# SCH_SIM7670G.net
KiCad netlist of a schematic drawn in Altium Designer
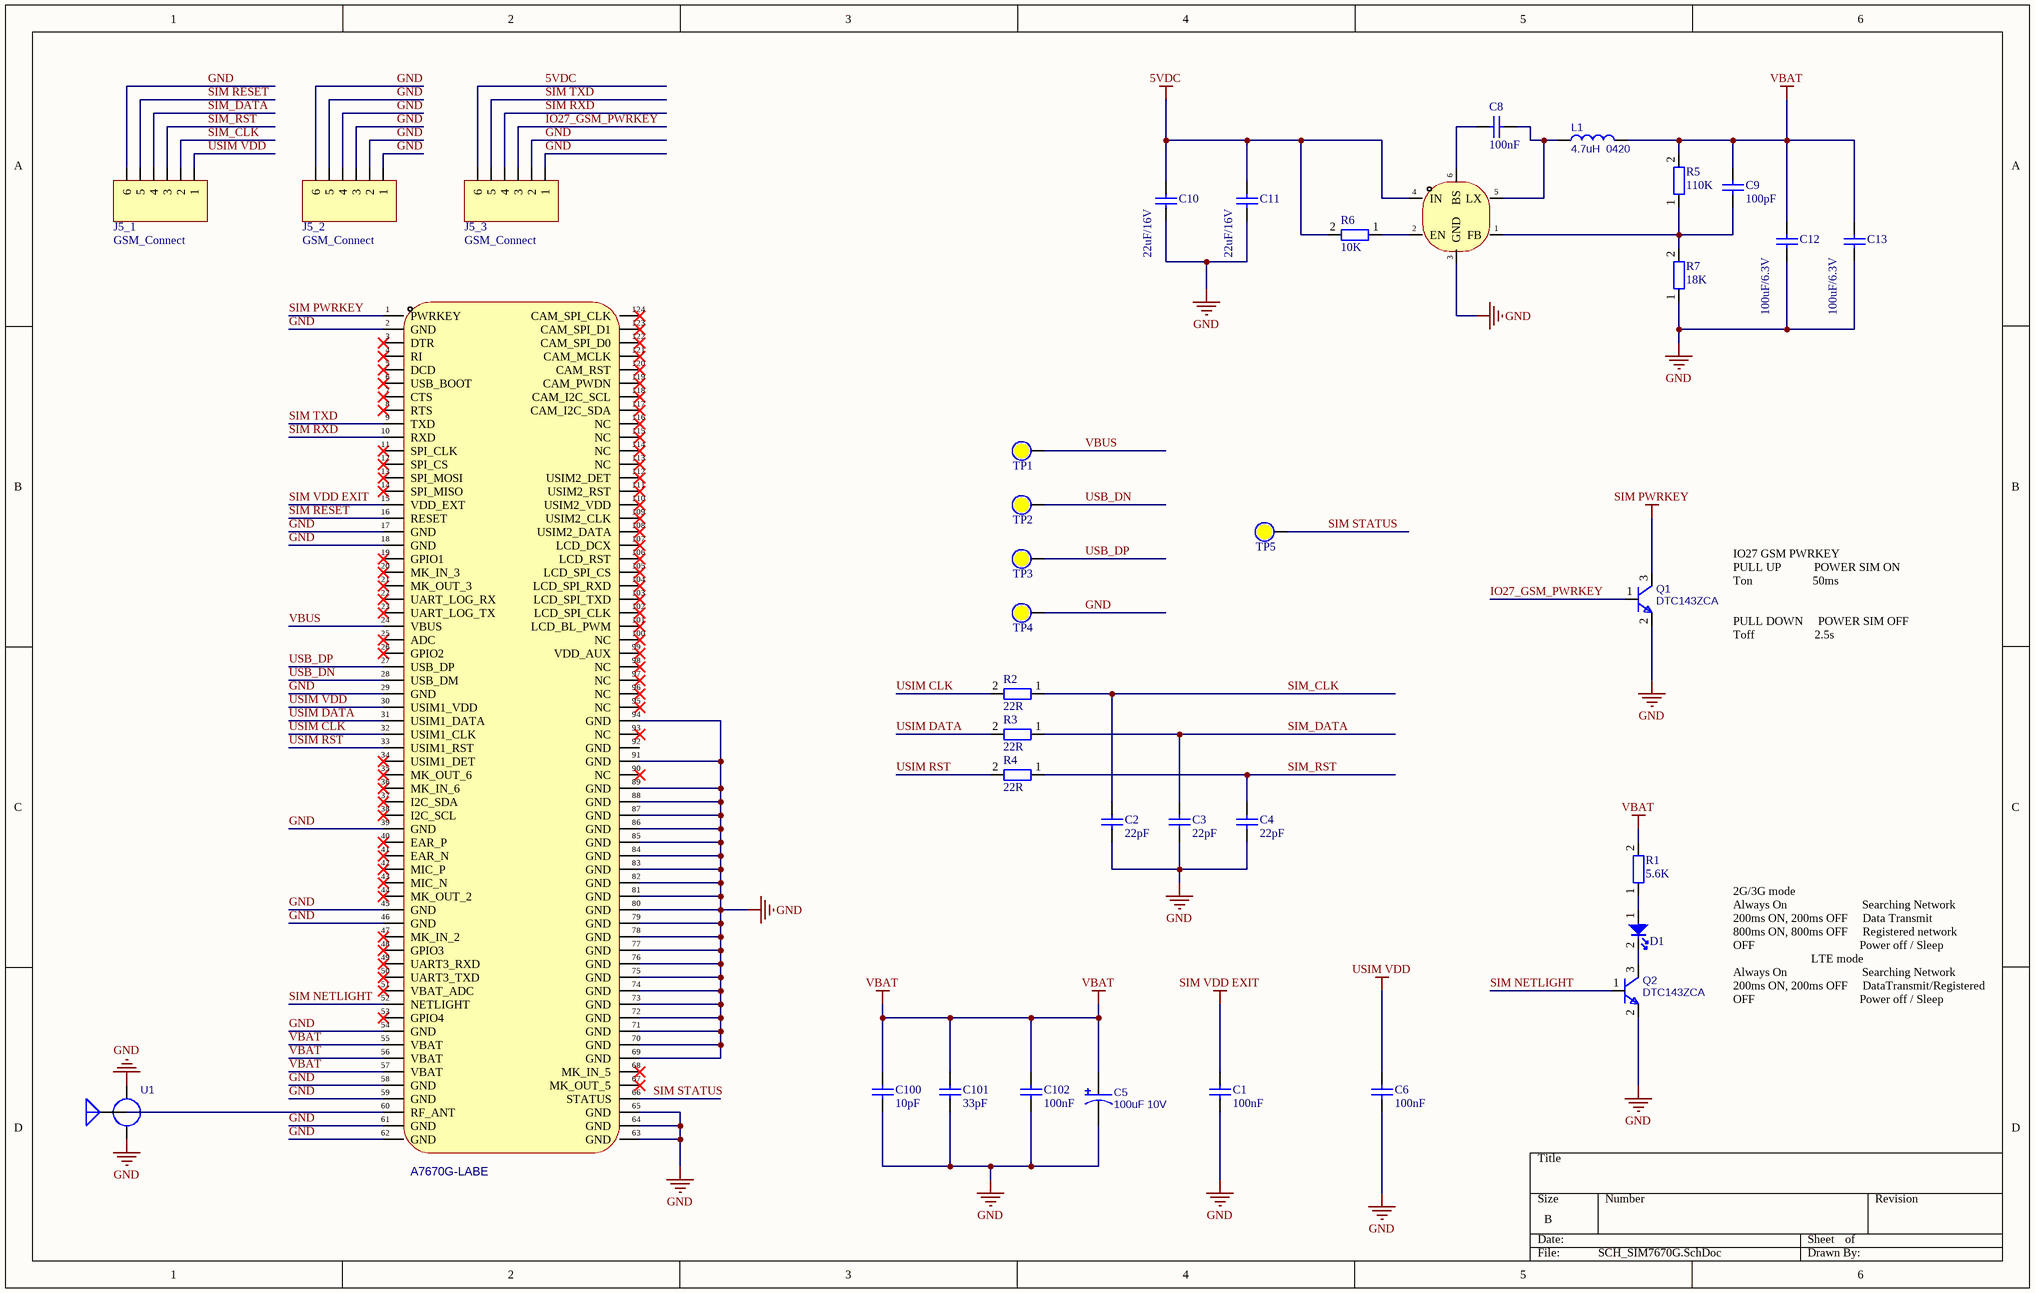
[diagram p0: SCH_SIM7670G.SchDoc]

(export (version "E")
  (design (tool "Eeschema 10.0.6"))
  (components
    (comp (ref "C1")
      (value "100nF")
      (footprint "CAP CERAMIC SMD 0402 TyPE 1005")
      (description "Capacitor")
      (libsource (lib "SCH_Library") (part "CAP104-100nF-50V"))
    )
    (comp (ref "C2")
      (value "22pF")
      (footprint "CAP CERAMIC SMD 0402 TyPE 1005")
      (description "Capacitor")
      (libsource (lib "SCH_Library") (part "CAP104-100nF-50V"))
    )
    (comp (ref "C3")
      (value "22pF")
      (footprint "CAP CERAMIC SMD 0402 TyPE 1005")
      (description "Capacitor")
      (libsource (lib "SCH_Library") (part "CAP104-100nF-50V"))
    )
    (comp (ref "C4")
      (value "22pF")
      (footprint "CAP CERAMIC SMD 0402 TyPE 1005")
      (description "Capacitor")
      (libsource (lib "SCH_Library") (part "CAP104-100nF-50V"))
    )
    (comp (ref "C5")
      (value "100uF 10V")
      (footprint "CAP TANTALUM SMD 3528-21 type B")
      (description "Aluminum Electrolytic Capacitors - Leaded ROHS")
      (fields
        (field (name "BOM_SUPPLIER PART") "C398835")
        (field (name "BOM_MANUFACTURER PART") "ERR1VM102G20OT")
        (field (name "CONTRIBUTOR") "LCSC")
      )
      (libsource (lib "SCH_AES_Library") (part "CAP ALU HOLD"))
    )
    (comp (ref "C6")
      (value "100nF")
      (footprint "CAP CERAMIC SMD 0402 TyPE 1005")
      (description "Capacitor")
      (libsource (lib "SCH_Library") (part "CAP104-100nF-50V"))
    )
    (comp (ref "C8")
      (value "100nF")
      (footprint "CAP CERAMIC SMD 0402 TyPE 1005")
      (description "Capacitor")
      (libsource (lib "SCH_Library") (part "CAP104-100nF-50V"))
    )
    (comp (ref "C9")
      (value "100pF")
      (footprint "CAP CERAMIC SMD 0402 TyPE 1005")
      (description "Capacitor")
      (libsource (lib "SCH_Library") (part "CAP104-100nF-50V"))
    )
    (comp (ref "C10")
      (value "22uF/16V")
      (footprint "CAP CERAMIC SMD 0603 TyPE 1608")
      (description "Capacitor")
      (libsource (lib "SCH_Library") (part "CAP104-100nF-50V"))
    )
    (comp (ref "C11")
      (value "22uF/16V")
      (footprint "CAP CERAMIC SMD 0603 TyPE 1608")
      (description "Capacitor")
      (libsource (lib "SCH_Library") (part "CAP104-100nF-50V"))
    )
    (comp (ref "C12")
      (value "100uF/6.3V")
      (footprint "CAP CERAMIC SMD 1206 TyPE 3216")
      (description "Capacitor")
      (libsource (lib "SCH_Library") (part "CAP104-100nF-50V"))
    )
    (comp (ref "C13")
      (value "100uF/6.3V")
      (footprint "CAP CERAMIC SMD 1206 TyPE 3216")
      (description "Capacitor")
      (libsource (lib "SCH_Library") (part "CAP104-100nF-50V"))
    )
    (comp (ref "C100")
      (value "10pF")
      (footprint "CAP CERAMIC SMD 0402 TyPE 1005")
      (description "Capacitor")
      (libsource (lib "SCH_Library") (part "CAP104-100nF-50V"))
    )
    (comp (ref "C101")
      (value "33pF")
      (footprint "CAP CERAMIC SMD 0402 TyPE 1005")
      (description "Capacitor")
      (libsource (lib "SCH_Library") (part "CAP104-100nF-50V"))
    )
    (comp (ref "C102")
      (value "100nF")
      (footprint "CAP CERAMIC SMD 0402 TyPE 1005")
      (description "Capacitor")
      (libsource (lib "SCH_Library") (part "CAP104-100nF-50V"))
    )
    (comp (ref "D1")
      (value "LED")
      (footprint "LED SMD GREEN TYPE 0603")
      (description "Emerald 0805 Light Emitting Diodes (LED) ROHS")
      (libsource (lib "SCH_AES_Library") (part "LED SMD 0805"))
    )
    (comp (ref "J5_1")
      (value "GSM_Connect")
      (footprint "CONNECTORS FEMALE HEADERS 1X6 2.0 TYPE STRAIGHT SMD")
      (description "Cắm")
      (libsource (lib "Altium_Lib") (part "JP 1x6 2.54 Duc Thang"))
    )
    (comp (ref "J5_2")
      (value "GSM_Connect")
      (footprint "CONNECTORS FEMALE HEADERS 1X6 2.0 TYPE STRAIGHT SMD")
      (description "Cắm")
      (libsource (lib "Altium_Lib") (part "JP 1x6 2.54 Duc Thang"))
    )
    (comp (ref "J5_3")
      (value "GSM_Connect")
      (footprint "CONNECTORS FEMALE HEADERS 1X6 2.0 TYPE STRAIGHT SMD")
      (description "Cắm")
      (libsource (lib "Altium_Lib") (part "JP 1x6 2.54 Duc Thang"))
    )
    (comp (ref "L1")
      (value "4.7uH  0420")
      (footprint "INDUCTORS SMD 0420")
      (fields
        (field (name "BOM_SUPPLIER PART") "C578001")
        (field (name "BOM_MANUFACTURER PART") "SCHF160808H47NJT")
        (field (name "CONTRIBUTOR") "LCSC")
      )
      (libsource (lib "SCH_AES_Library") (part "INDUCTORS SMD"))
    )
    (comp (ref "Q1")
      (value "DTC143ZCA")
      (footprint "SOT-23")
      (description "SOT-23 Bipolar Transistors npn - BJT ROHS")
      (fields
        (field (name "BOM_SUPPLIER PART") "C5156716")
        (field (name "BOM_MANUFACTURER PART") "MMBT3904")
        (field (name "CONTRIBUTOR") "lcsc")
      )
      (libsource (lib "SCH_AES_Library") (part "TRANSISTOR SMD NPN"))
    )
    (comp (ref "Q2")
      (value "DTC143ZCA")
      (footprint "SOT-23")
      (description "SOT-23 Bipolar Transistors npn - BJT ROHS")
      (fields
        (field (name "BOM_SUPPLIER PART") "C5156716")
        (field (name "BOM_MANUFACTURER PART") "MMBT3904")
        (field (name "CONTRIBUTOR") "lcsc")
      )
      (libsource (lib "SCH_AES_Library") (part "TRANSISTOR SMD NPN"))
    )
    (comp (ref "R1")
      (value "5.6K")
      (footprint "RES CHIPS SMD 0402 TYPE 1005")
      (description "±1% - Chip Resistor - Surface Mount ROHS")
      (libsource (lib "SCH_Library") (part "RES 0603 1%_"))
    )
    (comp (ref "R2")
      (value "22R")
      (footprint "RES CHIPS SMD 0402 TYPE 1005")
      (description "±1% - Chip Resistor - Surface Mount ROHS")
      (libsource (lib "SCH_Library") (part "RES 0603 1%_"))
    )
    (comp (ref "R3")
      (value "22R")
      (footprint "RES CHIPS SMD 0402 TYPE 1005")
      (description "±1% - Chip Resistor - Surface Mount ROHS")
      (libsource (lib "SCH_Library") (part "RES 0603 1%_"))
    )
    (comp (ref "R4")
      (value "22R")
      (footprint "RES CHIPS SMD 0402 TYPE 1005")
      (description "±1% - Chip Resistor - Surface Mount ROHS")
      (libsource (lib "SCH_Library") (part "RES 0603 1%_"))
    )
    (comp (ref "R5")
      (value "110K")
      (footprint "RES CHIPS SMD 0402 TYPE 1005")
      (description "±1% - Chip Resistor - Surface Mount ROHS")
      (libsource (lib "SCH_Library") (part "RES 0603 1%_"))
    )
    (comp (ref "R6")
      (value "10K")
      (footprint "RES CHIPS SMD 0402 TYPE 1005")
      (description "±1% - Chip Resistor - Surface Mount ROHS")
      (libsource (lib "SCH_Library") (part "RES 0603 1%_"))
    )
    (comp (ref "R7")
      (value "18K")
      (footprint "RES CHIPS SMD 0402 TYPE 1005")
      (description "±1% - Chip Resistor - Surface Mount ROHS")
      (libsource (lib "SCH_Library") (part "RES 0603 1%_"))
    )
    (comp (ref "TP1")
      (value "~")
      (footprint "TEST POINT 4")
      (description "Test Point")
      (libsource (lib "SCH_AES_Library") (part "TEST POINT"))
    )
    (comp (ref "TP2")
      (value "~")
      (footprint "TEST POINT 4")
      (description "Test Point")
      (libsource (lib "SCH_AES_Library") (part "TEST POINT"))
    )
    (comp (ref "TP3")
      (value "~")
      (footprint "TEST POINT 4")
      (description "Test Point")
      (libsource (lib "SCH_AES_Library") (part "TEST POINT"))
    )
    (comp (ref "TP4")
      (value "~")
      (footprint "TEST POINT 4")
      (description "Test Point")
      (libsource (lib "SCH_AES_Library") (part "TEST POINT"))
    )
    (comp (ref "TP5")
      (value "~")
      (footprint "TEST POINT 4")
      (description "Test Point")
      (libsource (lib "SCH_AES_Library") (part "TEST POINT"))
    )
    (comp (ref "U1")
      (value "~")
      (footprint "CONNECTORS RF SMD TYPE IPEX")
      (description "SMD RF Connectors / Coaxial Connectors ROHS")
      (fields
        (field (name "BOM_SUPPLIER PART") "C3151745")
        (field (name "BOM_MANUFACTURER PART") "IPEX1-TXZ 142")
        (field (name "CONTRIBUTOR") "lcsc")
      )
      (libsource (lib "SCH_AES_Library") (part "CONNECTORS RF SMD"))
    )
    (comp (ref "U2")
      (value "A7670G-LABE")
      (footprint "Modules SIM7670G")
      (fields (field (name "MANUFACTURER") "SIMCOM(芯讯通无线科技)"))
      (libsource (lib "SCH_AES_Library") (part "MODULES SIM A7670G-LABE"))
    )
    (comp (ref "U3")
      (value "SY8105IADC")
      (footprint "SOT-23-6")
      (fields (field (name "MANUFACTURER") "silergy(矽力杰)"))
      (libsource (lib "SCH_AES_Library") (part "SY8105IADC"))
    )
  )
  (nets
    (net (code "1") (name "/IO27_GSM_PWRKEY") (class "Default")
      (node (ref "J5_3") (pin "3") (pinfunction "3_3") (pintype "passive"))
      (node (ref "Q1") (pin "1") (pinfunction "B_1") (pintype "passive"))
    )
    (net (code "2") (name "/SIM NETLIGHT") (class "Default")
      (node (ref "Q2") (pin "1") (pinfunction "B_1") (pintype "passive"))
      (node (ref "U2") (pin "52") (pinfunction "NETLIGHT_52") (pintype "passive"))
    )
    (net (code "3") (name "/SIM RESET") (class "Default")
      (node (ref "J5_1") (pin "5") (pinfunction "5_5") (pintype "passive"))
      (node (ref "U2") (pin "16") (pinfunction "RESET_16") (pintype "passive"))
    )
    (net (code "4") (name "/SIM RXD") (class "Default")
      (node (ref "J5_3") (pin "4") (pinfunction "4_4") (pintype "passive"))
      (node (ref "U2") (pin "10") (pinfunction "RXD_10") (pintype "passive"))
    )
    (net (code "5") (name "/SIM STATUS") (class "Default")
      (node (ref "TP5") (pin "0") (pinfunction "0_0") (pintype "passive"))
      (node (ref "U2") (pin "66") (pinfunction "STATUS_66") (pintype "passive"))
    )
    (net (code "6") (name "/SIM TXD") (class "Default")
      (node (ref "J5_3") (pin "5") (pinfunction "5_5") (pintype "passive"))
      (node (ref "U2") (pin "9") (pinfunction "TXD_9") (pintype "passive"))
    )
    (net (code "7") (name "/SIM_CLK") (class "Default")
      (node (ref "C2") (pin "1") (pinfunction "1_1") (pintype "passive"))
      (node (ref "J5_1") (pin "2") (pinfunction "2_2") (pintype "passive"))
      (node (ref "R2") (pin "1") (pinfunction "1_1") (pintype "passive"))
    )
    (net (code "8") (name "/SIM_DATA") (class "Default")
      (node (ref "C3") (pin "2") (pinfunction "2_2") (pintype "passive"))
      (node (ref "J5_1") (pin "4") (pinfunction "4_4") (pintype "passive"))
      (node (ref "R3") (pin "1") (pinfunction "1_1") (pintype "passive"))
    )
    (net (code "9") (name "/SIM_RST") (class "Default")
      (node (ref "C4") (pin "2") (pinfunction "2_2") (pintype "passive"))
      (node (ref "J5_1") (pin "3") (pinfunction "3_3") (pintype "passive"))
      (node (ref "R4") (pin "1") (pinfunction "1_1") (pintype "passive"))
    )
    (net (code "10") (name "/USB_DN") (class "Default")
      (node (ref "TP2") (pin "0") (pinfunction "0_0") (pintype "passive"))
      (node (ref "U2") (pin "28") (pinfunction "USB_DM_28") (pintype "passive"))
    )
    (net (code "11") (name "/USB_DP") (class "Default")
      (node (ref "TP3") (pin "0") (pinfunction "0_0") (pintype "passive"))
      (node (ref "U2") (pin "27") (pinfunction "USB_DP_27") (pintype "passive"))
    )
    (net (code "12") (name "/USIM CLK") (class "Default")
      (node (ref "R2") (pin "2") (pinfunction "2_2") (pintype "passive"))
      (node (ref "U2") (pin "32") (pinfunction "USIM1_CLK_32") (pintype "passive"))
    )
    (net (code "13") (name "/USIM DATA") (class "Default")
      (node (ref "R3") (pin "2") (pinfunction "2_2") (pintype "passive"))
      (node (ref "U2") (pin "31") (pinfunction "USIM1_DATA_31") (pintype "passive"))
    )
    (net (code "14") (name "/USIM RST") (class "Default")
      (node (ref "R4") (pin "2") (pinfunction "2_2") (pintype "passive"))
      (node (ref "U2") (pin "33") (pinfunction "USIM1_RST_33") (pintype "passive"))
    )
    (net (code "15") (name "/VBUS") (class "Default")
      (node (ref "TP1") (pin "0") (pinfunction "0_0") (pintype "passive"))
      (node (ref "U2") (pin "24") (pinfunction "VBUS_24") (pintype "passive"))
    )
    (net (code "16") (name "5VDC") (class "Default")
      (node (ref "C10") (pin "2") (pinfunction "2_2") (pintype "passive"))
      (node (ref "C11") (pin "2") (pinfunction "2_2") (pintype "passive"))
      (node (ref "J5_3") (pin "6") (pinfunction "6_6") (pintype "passive"))
      (node (ref "R6") (pin "2") (pinfunction "2_2") (pintype "passive"))
      (node (ref "U3") (pin "4") (pinfunction "IN_4") (pintype "passive"))
    )
    (net (code "17") (name "GND") (class "Default")
      (node (ref "C1") (pin "1") (pinfunction "1_1") (pintype "passive"))
      (node (ref "C10") (pin "1") (pinfunction "1_1") (pintype "passive"))
      (node (ref "C100") (pin "1") (pinfunction "1_1") (pintype "passive"))
      (node (ref "C101") (pin "1") (pinfunction "1_1") (pintype "passive"))
      (node (ref "C102") (pin "1") (pinfunction "1_1") (pintype "passive"))
      (node (ref "C11") (pin "1") (pinfunction "1_1") (pintype "passive"))
      (node (ref "C12") (pin "1") (pinfunction "1_1") (pintype "passive"))
      (node (ref "C13") (pin "1") (pinfunction "1_1") (pintype "passive"))
      (node (ref "C2") (pin "2") (pinfunction "2_2") (pintype "passive"))
      (node (ref "C3") (pin "1") (pinfunction "1_1") (pintype "passive"))
      (node (ref "C4") (pin "1") (pinfunction "1_1") (pintype "passive"))
      (node (ref "C5") (pin "2") (pinfunction "2_2") (pintype "passive"))
      (node (ref "C6") (pin "1") (pinfunction "1_1") (pintype "passive"))
      (node (ref "J5_1") (pin "6") (pinfunction "6_6") (pintype "passive"))
      (node (ref "J5_2") (pin "1") (pinfunction "1_1") (pintype "passive"))
      (node (ref "J5_2") (pin "2") (pinfunction "2_2") (pintype "passive"))
      (node (ref "J5_2") (pin "3") (pinfunction "3_3") (pintype "passive"))
      (node (ref "J5_2") (pin "4") (pinfunction "4_4") (pintype "passive"))
      (node (ref "J5_2") (pin "5") (pinfunction "5_5") (pintype "passive"))
      (node (ref "J5_2") (pin "6") (pinfunction "6_6") (pintype "passive"))
      (node (ref "J5_3") (pin "1") (pinfunction "1_1") (pintype "passive"))
      (node (ref "J5_3") (pin "2") (pinfunction "2_2") (pintype "passive"))
      (node (ref "Q1") (pin "2") (pinfunction "E_2") (pintype "passive"))
      (node (ref "Q2") (pin "2") (pinfunction "E_2") (pintype "passive"))
      (node (ref "R7") (pin "1") (pinfunction "1_1") (pintype "passive"))
      (node (ref "TP4") (pin "0") (pinfunction "0_0") (pintype "passive"))
      (node (ref "U1") (pin "2") (pinfunction "2_2") (pintype "passive"))
      (node (ref "U1") (pin "3") (pinfunction "3_3") (pintype "passive"))
      (node (ref "U2") (pin "17") (pinfunction "GND_17") (pintype "passive"))
      (node (ref "U2") (pin "18") (pinfunction "GND_18") (pintype "passive"))
      (node (ref "U2") (pin "2") (pinfunction "GND_2") (pintype "passive"))
      (node (ref "U2") (pin "29") (pinfunction "GND_29") (pintype "passive"))
      (node (ref "U2") (pin "39") (pinfunction "GND_39") (pintype "passive"))
      (node (ref "U2") (pin "45") (pinfunction "GND_45") (pintype "passive"))
      (node (ref "U2") (pin "46") (pinfunction "GND_46") (pintype "passive"))
      (node (ref "U2") (pin "54") (pinfunction "GND_54") (pintype "passive"))
      (node (ref "U2") (pin "58") (pinfunction "GND_58") (pintype "passive"))
      (node (ref "U2") (pin "59") (pinfunction "GND_59") (pintype "passive"))
      (node (ref "U2") (pin "61") (pinfunction "GND_61") (pintype "passive"))
      (node (ref "U2") (pin "62") (pinfunction "GND_62") (pintype "passive"))
      (node (ref "U2") (pin "63") (pinfunction "GND_63") (pintype "passive"))
      (node (ref "U2") (pin "64") (pinfunction "GND_64") (pintype "passive"))
      (node (ref "U2") (pin "65") (pinfunction "GND_65") (pintype "passive"))
      (node (ref "U2") (pin "69") (pinfunction "GND_69") (pintype "passive"))
      (node (ref "U2") (pin "70") (pinfunction "GND_70") (pintype "passive"))
      (node (ref "U2") (pin "71") (pinfunction "GND_71") (pintype "passive"))
      (node (ref "U2") (pin "72") (pinfunction "GND_72") (pintype "passive"))
      (node (ref "U2") (pin "73") (pinfunction "GND_73") (pintype "passive"))
      (node (ref "U2") (pin "74") (pinfunction "GND_74") (pintype "passive"))
      (node (ref "U2") (pin "75") (pinfunction "GND_75") (pintype "passive"))
      (node (ref "U2") (pin "76") (pinfunction "GND_76") (pintype "passive"))
      (node (ref "U2") (pin "77") (pinfunction "GND_77") (pintype "passive"))
      (node (ref "U2") (pin "78") (pinfunction "GND_78") (pintype "passive"))
      (node (ref "U2") (pin "79") (pinfunction "GND_79") (pintype "passive"))
      (node (ref "U2") (pin "80") (pinfunction "GND_80") (pintype "passive"))
      (node (ref "U2") (pin "81") (pinfunction "GND_81") (pintype "passive"))
      (node (ref "U2") (pin "82") (pinfunction "GND_82") (pintype "passive"))
      (node (ref "U2") (pin "83") (pinfunction "GND_83") (pintype "passive"))
      (node (ref "U2") (pin "84") (pinfunction "GND_84") (pintype "passive"))
      (node (ref "U2") (pin "85") (pinfunction "GND_85") (pintype "passive"))
      (node (ref "U2") (pin "86") (pinfunction "GND_86") (pintype "passive"))
      (node (ref "U2") (pin "87") (pinfunction "GND_87") (pintype "passive"))
      (node (ref "U2") (pin "88") (pinfunction "GND_88") (pintype "passive"))
      (node (ref "U2") (pin "89") (pinfunction "GND_89") (pintype "passive"))
      (node (ref "U2") (pin "91") (pinfunction "GND_91") (pintype "passive"))
      (node (ref "U2") (pin "94") (pinfunction "GND_94") (pintype "passive"))
      (node (ref "U3") (pin "3") (pinfunction "GND_3") (pintype "passive"))
    )
    (net (code "18") (name "Net-(D1-Pad1)") (class "Default")
      (node (ref "D1") (pin "1") (pinfunction "1_1") (pintype "passive"))
      (node (ref "R1") (pin "1") (pinfunction "1_1") (pintype "passive"))
    )
    (net (code "19") (name "Net-(Q2-C)") (class "Default")
      (node (ref "D1") (pin "2") (pinfunction "2_2") (pintype "passive"))
      (node (ref "Q2") (pin "3") (pinfunction "C_3") (pintype "passive"))
    )
    (net (code "20") (name "Net-(U2-RF_ANT)") (class "Default")
      (node (ref "U1") (pin "1") (pinfunction "1_1") (pintype "passive"))
      (node (ref "U2") (pin "60") (pinfunction "RF_ANT_60") (pintype "passive"))
    )
    (net (code "21") (name "Net-(U3-BS)") (class "Default")
      (node (ref "C8") (pin "2") (pinfunction "2_2") (pintype "passive"))
      (node (ref "U3") (pin "6") (pinfunction "BS_6") (pintype "passive"))
    )
    (net (code "22") (name "Net-(U3-EN)") (class "Default")
      (node (ref "R6") (pin "1") (pinfunction "1_1") (pintype "passive"))
      (node (ref "U3") (pin "2") (pinfunction "EN_2") (pintype "passive"))
    )
    (net (code "23") (name "Net-(U3-FB)") (class "Default")
      (node (ref "C9") (pin "1") (pinfunction "1_1") (pintype "passive"))
      (node (ref "R5") (pin "1") (pinfunction "1_1") (pintype "passive"))
      (node (ref "R7") (pin "2") (pinfunction "2_2") (pintype "passive"))
      (node (ref "U3") (pin "1") (pinfunction "FB_1") (pintype "passive"))
    )
    (net (code "24") (name "Net-(U3-LX)") (class "Default")
      (node (ref "C8") (pin "1") (pinfunction "1_1") (pintype "passive"))
      (node (ref "L1") (pin "1") (pinfunction "1_1") (pintype "passive"))
      (node (ref "U3") (pin "5") (pinfunction "LX_5") (pintype "passive"))
    )
    (net (code "25") (name "SIM PWRKEY") (class "Default")
      (node (ref "Q1") (pin "3") (pinfunction "C_3") (pintype "passive"))
      (node (ref "U2") (pin "1") (pinfunction "PWRKEY_1") (pintype "passive"))
    )
    (net (code "26") (name "SIM VDD EXIT") (class "Default")
      (node (ref "C1") (pin "2") (pinfunction "2_2") (pintype "passive"))
      (node (ref "U2") (pin "15") (pinfunction "VDD_EXT_15") (pintype "passive"))
    )
    (net (code "27") (name "USIM VDD") (class "Default")
      (node (ref "C6") (pin "2") (pinfunction "2_2") (pintype "passive"))
      (node (ref "J5_1") (pin "1") (pinfunction "1_1") (pintype "passive"))
      (node (ref "U2") (pin "30") (pinfunction "USIM1_VDD_30") (pintype "passive"))
    )
    (net (code "28") (name "VBAT") (class "Default")
      (node (ref "C100") (pin "2") (pinfunction "2_2") (pintype "passive"))
      (node (ref "C101") (pin "2") (pinfunction "2_2") (pintype "passive"))
      (node (ref "C102") (pin "2") (pinfunction "2_2") (pintype "passive"))
      (node (ref "C12") (pin "2") (pinfunction "2_2") (pintype "passive"))
      (node (ref "C13") (pin "2") (pinfunction "2_2") (pintype "passive"))
      (node (ref "C5") (pin "1") (pinfunction "1_1") (pintype "passive"))
      (node (ref "C9") (pin "2") (pinfunction "2_2") (pintype "passive"))
      (node (ref "L1") (pin "2") (pinfunction "2_2") (pintype "passive"))
      (node (ref "R1") (pin "2") (pinfunction "2_2") (pintype "passive"))
      (node (ref "R5") (pin "2") (pinfunction "2_2") (pintype "passive"))
      (node (ref "U2") (pin "55") (pinfunction "VBAT_55") (pintype "passive"))
      (node (ref "U2") (pin "56") (pinfunction "VBAT_56") (pintype "passive"))
      (node (ref "U2") (pin "57") (pinfunction "VBAT_57") (pintype "passive"))
    )
    (net (code "29") (name "unconnected-(U2-ADC-Pad25)") (class "Default")
      (node (ref "U2") (pin "25") (pinfunction "ADC_25") (pintype "passive+no_connect"))
    )
    (net (code "30") (name "unconnected-(U2-CAM_I2C_SCL-Pad118)") (class "Default")
      (node (ref "U2") (pin "118") (pinfunction "CAM_I2C_SCL_118") (pintype "passive+no_connect"))
    )
    (net (code "31") (name "unconnected-(U2-CAM_I2C_SDA-Pad117)") (class "Default")
      (node (ref "U2") (pin "117") (pinfunction "CAM_I2C_SDA_117") (pintype "passive+no_connect"))
    )
    (net (code "32") (name "unconnected-(U2-CAM_MCLK-Pad121)") (class "Default")
      (node (ref "U2") (pin "121") (pinfunction "CAM_MCLK_121") (pintype "passive+no_connect"))
    )
    (net (code "33") (name "unconnected-(U2-CAM_PWDN-Pad119)") (class "Default")
      (node (ref "U2") (pin "119") (pinfunction "CAM_PWDN_119") (pintype "passive+no_connect"))
    )
    (net (code "34") (name "unconnected-(U2-CAM_RST-Pad120)") (class "Default")
      (node (ref "U2") (pin "120") (pinfunction "CAM_RST_120") (pintype "passive+no_connect"))
    )
    (net (code "35") (name "unconnected-(U2-CAM_SPI_CLK-Pad124)") (class "Default")
      (node (ref "U2") (pin "124") (pinfunction "CAM_SPI_CLK_124") (pintype "passive+no_connect"))
    )
    (net (code "36") (name "unconnected-(U2-CAM_SPI_D0-Pad122)") (class "Default")
      (node (ref "U2") (pin "122") (pinfunction "CAM_SPI_D0_122") (pintype "passive+no_connect"))
    )
    (net (code "37") (name "unconnected-(U2-CAM_SPI_D1-Pad123)") (class "Default")
      (node (ref "U2") (pin "123") (pinfunction "CAM_SPI_D1_123") (pintype "passive+no_connect"))
    )
    (net (code "38") (name "unconnected-(U2-CTS-Pad7)") (class "Default")
      (node (ref "U2") (pin "7") (pinfunction "CTS_7") (pintype "passive+no_connect"))
    )
    (net (code "39") (name "unconnected-(U2-DCD-Pad5)") (class "Default")
      (node (ref "U2") (pin "5") (pinfunction "DCD_5") (pintype "passive+no_connect"))
    )
    (net (code "40") (name "unconnected-(U2-DTR-Pad3)") (class "Default")
      (node (ref "U2") (pin "3") (pinfunction "DTR_3") (pintype "passive+no_connect"))
    )
    (net (code "41") (name "unconnected-(U2-EAR_N-Pad41)") (class "Default")
      (node (ref "U2") (pin "41") (pinfunction "EAR_N_41") (pintype "passive+no_connect"))
    )
    (net (code "42") (name "unconnected-(U2-EAR_P-Pad40)") (class "Default")
      (node (ref "U2") (pin "40") (pinfunction "EAR_P_40") (pintype "passive+no_connect"))
    )
    (net (code "43") (name "unconnected-(U2-GND-Pad92)") (class "Default")
      (node (ref "U2") (pin "92") (pinfunction "GND_92") (pintype "passive"))
    )
    (net (code "44") (name "unconnected-(U2-GPIO1-Pad19)") (class "Default")
      (node (ref "U2") (pin "19") (pinfunction "GPIO1_19") (pintype "passive+no_connect"))
    )
    (net (code "45") (name "unconnected-(U2-GPIO2-Pad26)") (class "Default")
      (node (ref "U2") (pin "26") (pinfunction "GPIO2_26") (pintype "passive+no_connect"))
    )
    (net (code "46") (name "unconnected-(U2-GPIO3-Pad48)") (class "Default")
      (node (ref "U2") (pin "48") (pinfunction "GPIO3_48") (pintype "passive+no_connect"))
    )
    (net (code "47") (name "unconnected-(U2-GPIO4-Pad53)") (class "Default")
      (node (ref "U2") (pin "53") (pinfunction "GPIO4_53") (pintype "passive+no_connect"))
    )
    (net (code "48") (name "unconnected-(U2-I2C_SCL-Pad38)") (class "Default")
      (node (ref "U2") (pin "38") (pinfunction "I2C_SCL_38") (pintype "passive+no_connect"))
    )
    (net (code "49") (name "unconnected-(U2-I2C_SDA-Pad37)") (class "Default")
      (node (ref "U2") (pin "37") (pinfunction "I2C_SDA_37") (pintype "passive+no_connect"))
    )
    (net (code "50") (name "unconnected-(U2-LCD_BL_PWM-Pad101)") (class "Default")
      (node (ref "U2") (pin "101") (pinfunction "LCD_BL_PWM_101") (pintype "passive+no_connect"))
    )
    (net (code "51") (name "unconnected-(U2-LCD_DCX-Pad107)") (class "Default")
      (node (ref "U2") (pin "107") (pinfunction "LCD_DCX_107") (pintype "passive+no_connect"))
    )
    (net (code "52") (name "unconnected-(U2-LCD_RST-Pad106)") (class "Default")
      (node (ref "U2") (pin "106") (pinfunction "LCD_RST_106") (pintype "passive+no_connect"))
    )
    (net (code "53") (name "unconnected-(U2-LCD_SPI_CLK-Pad102)") (class "Default")
      (node (ref "U2") (pin "102") (pinfunction "LCD_SPI_CLK_102") (pintype "passive+no_connect"))
    )
    (net (code "54") (name "unconnected-(U2-LCD_SPI_CS-Pad105)") (class "Default")
      (node (ref "U2") (pin "105") (pinfunction "LCD_SPI_CS_105") (pintype "passive+no_connect"))
    )
    (net (code "55") (name "unconnected-(U2-LCD_SPI_RXD-Pad104)") (class "Default")
      (node (ref "U2") (pin "104") (pinfunction "LCD_SPI_RXD_104") (pintype "passive+no_connect"))
    )
    (net (code "56") (name "unconnected-(U2-LCD_SPI_TXD-Pad103)") (class "Default")
      (node (ref "U2") (pin "103") (pinfunction "LCD_SPI_TXD_103") (pintype "passive+no_connect"))
    )
    (net (code "57") (name "unconnected-(U2-MIC_N-Pad43)") (class "Default")
      (node (ref "U2") (pin "43") (pinfunction "MIC_N_43") (pintype "passive+no_connect"))
    )
    (net (code "58") (name "unconnected-(U2-MIC_P-Pad42)") (class "Default")
      (node (ref "U2") (pin "42") (pinfunction "MIC_P_42") (pintype "passive+no_connect"))
    )
    (net (code "59") (name "unconnected-(U2-MK_IN_2-Pad47)") (class "Default")
      (node (ref "U2") (pin "47") (pinfunction "MK_IN_2_47") (pintype "passive+no_connect"))
    )
    (net (code "60") (name "unconnected-(U2-MK_IN_3-Pad20)") (class "Default")
      (node (ref "U2") (pin "20") (pinfunction "MK_IN_3_20") (pintype "passive+no_connect"))
    )
    (net (code "61") (name "unconnected-(U2-MK_IN_5-Pad68)") (class "Default")
      (node (ref "U2") (pin "68") (pinfunction "MK_IN_5_68") (pintype "passive+no_connect"))
    )
    (net (code "62") (name "unconnected-(U2-MK_IN_6-Pad36)") (class "Default")
      (node (ref "U2") (pin "36") (pinfunction "MK_IN_6_36") (pintype "passive+no_connect"))
    )
    (net (code "63") (name "unconnected-(U2-MK_OUT_2-Pad44)") (class "Default")
      (node (ref "U2") (pin "44") (pinfunction "MK_OUT_2_44") (pintype "passive+no_connect"))
    )
    (net (code "64") (name "unconnected-(U2-MK_OUT_3-Pad21)") (class "Default")
      (node (ref "U2") (pin "21") (pinfunction "MK_OUT_3_21") (pintype "passive+no_connect"))
    )
    (net (code "65") (name "unconnected-(U2-MK_OUT_5-Pad67)") (class "Default")
      (node (ref "U2") (pin "67") (pinfunction "MK_OUT_5_67") (pintype "passive+no_connect"))
    )
    (net (code "66") (name "unconnected-(U2-MK_OUT_6-Pad35)") (class "Default")
      (node (ref "U2") (pin "35") (pinfunction "MK_OUT_6_35") (pintype "passive+no_connect"))
    )
    (net (code "67") (name "unconnected-(U2-NC-Pad90)") (class "Default")
      (node (ref "U2") (pin "90") (pinfunction "NC_90") (pintype "passive+no_connect"))
    )
    (net (code "68") (name "unconnected-(U2-NC-Pad93)") (class "Default")
      (node (ref "U2") (pin "93") (pinfunction "NC_93") (pintype "passive+no_connect"))
    )
    (net (code "69") (name "unconnected-(U2-NC-Pad95)") (class "Default")
      (node (ref "U2") (pin "95") (pinfunction "NC_95") (pintype "passive+no_connect"))
    )
    (net (code "70") (name "unconnected-(U2-NC-Pad96)") (class "Default")
      (node (ref "U2") (pin "96") (pinfunction "NC_96") (pintype "passive+no_connect"))
    )
    (net (code "71") (name "unconnected-(U2-NC-Pad97)") (class "Default")
      (node (ref "U2") (pin "97") (pinfunction "NC_97") (pintype "passive+no_connect"))
    )
    (net (code "72") (name "unconnected-(U2-NC-Pad98)") (class "Default")
      (node (ref "U2") (pin "98") (pinfunction "NC_98") (pintype "passive+no_connect"))
    )
    (net (code "73") (name "unconnected-(U2-NC-Pad100)") (class "Default")
      (node (ref "U2") (pin "100") (pinfunction "NC_100") (pintype "passive+no_connect"))
    )
    (net (code "74") (name "unconnected-(U2-NC-Pad113)") (class "Default")
      (node (ref "U2") (pin "113") (pinfunction "NC_113") (pintype "passive+no_connect"))
    )
    (net (code "75") (name "unconnected-(U2-NC-Pad114)") (class "Default")
      (node (ref "U2") (pin "114") (pinfunction "NC_114") (pintype "passive+no_connect"))
    )
    (net (code "76") (name "unconnected-(U2-NC-Pad115)") (class "Default")
      (node (ref "U2") (pin "115") (pinfunction "NC_115") (pintype "passive+no_connect"))
    )
    (net (code "77") (name "unconnected-(U2-NC-Pad116)") (class "Default")
      (node (ref "U2") (pin "116") (pinfunction "NC_116") (pintype "passive+no_connect"))
    )
    (net (code "78") (name "unconnected-(U2-RI-Pad4)") (class "Default")
      (node (ref "U2") (pin "4") (pinfunction "RI_4") (pintype "passive+no_connect"))
    )
    (net (code "79") (name "unconnected-(U2-RTS-Pad8)") (class "Default")
      (node (ref "U2") (pin "8") (pinfunction "RTS_8") (pintype "passive+no_connect"))
    )
    (net (code "80") (name "unconnected-(U2-SPI_CLK-Pad11)") (class "Default")
      (node (ref "U2") (pin "11") (pinfunction "SPI_CLK_11") (pintype "passive+no_connect"))
    )
    (net (code "81") (name "unconnected-(U2-SPI_CS-Pad12)") (class "Default")
      (node (ref "U2") (pin "12") (pinfunction "SPI_CS_12") (pintype "passive+no_connect"))
    )
    (net (code "82") (name "unconnected-(U2-SPI_MISO-Pad14)") (class "Default")
      (node (ref "U2") (pin "14") (pinfunction "SPI_MISO_14") (pintype "passive+no_connect"))
    )
    (net (code "83") (name "unconnected-(U2-SPI_MOSI-Pad13)") (class "Default")
      (node (ref "U2") (pin "13") (pinfunction "SPI_MOSI_13") (pintype "passive+no_connect"))
    )
    (net (code "84") (name "unconnected-(U2-UART3_RXD-Pad49)") (class "Default")
      (node (ref "U2") (pin "49") (pinfunction "UART3_RXD_49") (pintype "passive+no_connect"))
    )
    (net (code "85") (name "unconnected-(U2-UART3_TXD-Pad50)") (class "Default")
      (node (ref "U2") (pin "50") (pinfunction "UART3_TXD_50") (pintype "passive+no_connect"))
    )
    (net (code "86") (name "unconnected-(U2-UART_LOG_RX-Pad22)") (class "Default")
      (node (ref "U2") (pin "22") (pinfunction "UART_LOG_RX_22") (pintype "passive+no_connect"))
    )
    (net (code "87") (name "unconnected-(U2-UART_LOG_TX-Pad23)") (class "Default")
      (node (ref "U2") (pin "23") (pinfunction "UART_LOG_TX_23") (pintype "passive+no_connect"))
    )
    (net (code "88") (name "unconnected-(U2-USB_BOOT-Pad6)") (class "Default")
      (node (ref "U2") (pin "6") (pinfunction "USB_BOOT_6") (pintype "passive+no_connect"))
    )
    (net (code "89") (name "unconnected-(U2-USIM1_DET-Pad34)") (class "Default")
      (node (ref "U2") (pin "34") (pinfunction "USIM1_DET_34") (pintype "passive+no_connect"))
    )
    (net (code "90") (name "unconnected-(U2-USIM2_CLK-Pad109)") (class "Default")
      (node (ref "U2") (pin "109") (pinfunction "USIM2_CLK_109") (pintype "passive+no_connect"))
    )
    (net (code "91") (name "unconnected-(U2-USIM2_DATA-Pad108)") (class "Default")
      (node (ref "U2") (pin "108") (pinfunction "USIM2_DATA_108") (pintype "passive+no_connect"))
    )
    (net (code "92") (name "unconnected-(U2-USIM2_DET-Pad112)") (class "Default")
      (node (ref "U2") (pin "112") (pinfunction "USIM2_DET_112") (pintype "passive+no_connect"))
    )
    (net (code "93") (name "unconnected-(U2-USIM2_RST-Pad111)") (class "Default")
      (node (ref "U2") (pin "111") (pinfunction "USIM2_RST_111") (pintype "passive+no_connect"))
    )
    (net (code "94") (name "unconnected-(U2-USIM2_VDD-Pad110)") (class "Default")
      (node (ref "U2") (pin "110") (pinfunction "USIM2_VDD_110") (pintype "passive+no_connect"))
    )
    (net (code "95") (name "unconnected-(U2-VBAT_ADC-Pad51)") (class "Default")
      (node (ref "U2") (pin "51") (pinfunction "VBAT_ADC_51") (pintype "passive+no_connect"))
    )
    (net (code "96") (name "unconnected-(U2-VDD_AUX-Pad99)") (class "Default")
      (node (ref "U2") (pin "99") (pinfunction "VDD_AUX_99") (pintype "passive+no_connect"))
    )
  )
)
